# teensy_rfm69cw_nrf_lower.net
KiCad netlist of a schematic drawn in EAGLE
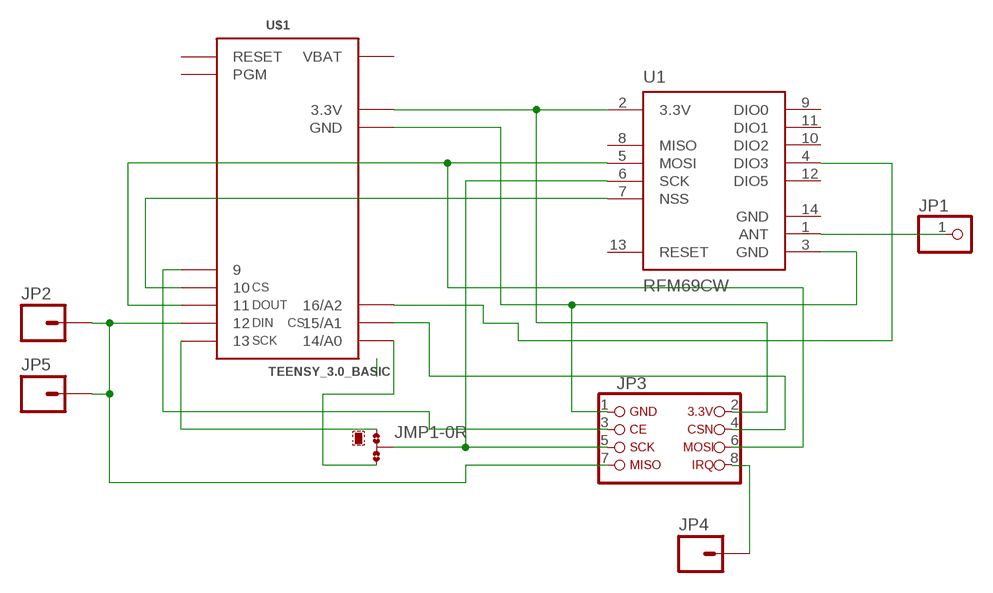
[diagram p0: schematic, sheet 1]

(export (version "E")
  (design (tool "Eeschema 10.0.6"))
  (components
    (comp (ref "JMP1")
      (value "0R-JUMPA")
      (footprint "eagle-import:A0R-JMP")
      (libsource (lib "eagle-import") (part "0R-JUMPA"))
    )
    (comp (ref "JP1")
      (value "PINHD-1X1")
      (footprint "eagle-import:1X01")
      (libsource (lib "eagle-import") (part "PINHD-1X1"))
    )
    (comp (ref "JP2")
      (value "M01SMD-4.5X1.5")
      (footprint "eagle-import:PAD-1.5X4.5")
      (libsource (lib "eagle-import") (part "M01SMD-4.5X1.5"))
    )
    (comp (ref "JP3")
      (value "NRF24")
      (footprint "eagle-import:NRF24")
      (libsource (lib "eagle-import") (part "NRF24"))
    )
    (comp (ref "JP4")
      (value "M01SMD-4.5X1.5")
      (footprint "eagle-import:PAD-1.5X4.5")
      (libsource (lib "eagle-import") (part "M01SMD-4.5X1.5"))
    )
    (comp (ref "JP5")
      (value "M01SMD-4.5X1.5")
      (footprint "eagle-import:PAD-1.5X4.5")
      (libsource (lib "eagle-import") (part "M01SMD-4.5X1.5"))
    )
    (comp (ref "U$1")
      (value "TEENSY_3.0_BASIC")
      (footprint "eagle-import:TEENSY_3.0_BASIC")
      (libsource (lib "eagle-import") (part "TEENSY_3.0_BASIC"))
    )
    (comp (ref "U1")
      (value "RFM69CW")
      (footprint "eagle-import:RFM69CW-XXXS2")
      (libsource (lib "eagle-import") (part "RFM69CW"))
    )
  )
  (nets
    (net (code "1") (name "/GND") (class "Default")
      (node (ref "U1") (pin "14") (pinfunction "GND_14") (pintype "power_in"))
    )
    (net (code "2") (name "/VBAT") (class "Default")
      (node (ref "U$1") (pin "VBAT") (pinfunction "VBAT_VBAT") (pintype "power_in"))
    )
    (net (code "3") (name "Net-(JMP1-Pad1)") (class "Default")
      (node (ref "JMP1") (pin "1") (pinfunction "1_1") (pintype "passive"))
      (node (ref "U$1") (pin "13") (pinfunction "13_13") (pintype "bidirectional"))
    )
    (net (code "4") (name "Net-(JMP1-Pad3)") (class "Default")
      (node (ref "JMP1") (pin "3") (pinfunction "3_3") (pintype "passive"))
      (node (ref "U$1") (pin "14/A0") (pinfunction "14/A0_14/A0") (pintype "bidirectional"))
    )
    (net (code "5") (name "Net-(JP2-1)") (class "Default")
      (node (ref "JP2") (pin "P$1") (pinfunction "1_P$1") (pintype "passive"))
      (node (ref "JP3") (pin "7") (pinfunction "7_7") (pintype "passive"))
      (node (ref "JP5") (pin "P$1") (pinfunction "1_P$1") (pintype "passive"))
      (node (ref "U$1") (pin "12") (pinfunction "12_12") (pintype "bidirectional"))
    )
    (net (code "6") (name "Net-(JP3-Pad3)") (class "Default")
      (node (ref "JP3") (pin "3") (pinfunction "3_3") (pintype "passive"))
      (node (ref "U$1") (pin "9") (pinfunction "9_9") (pintype "bidirectional"))
    )
    (net (code "7") (name "Net-(JP3-Pad4)") (class "Default")
      (node (ref "JP3") (pin "4") (pinfunction "4_4") (pintype "passive"))
      (node (ref "U$1") (pin "15/A1") (pinfunction "15/A1_15/A1") (pintype "bidirectional"))
    )
    (net (code "8") (name "Net-(JP4-1)") (class "Default")
      (node (ref "JP3") (pin "8") (pinfunction "8_8") (pintype "passive"))
      (node (ref "JP4") (pin "P$1") (pinfunction "1_P$1") (pintype "passive"))
    )
    (net (code "9") (name "Net-(U$1-3.3V)") (class "Default")
      (node (ref "JP3") (pin "2") (pinfunction "2_2") (pintype "passive"))
      (node (ref "U$1") (pin "3.3V1") (pinfunction "3.3V_3.3V1") (pintype "power_in"))
      (node (ref "U1") (pin "2") (pinfunction "3.3V_2") (pintype "power_in"))
    )
    (net (code "10") (name "Net-(U$1-GND)") (class "Default")
      (node (ref "JP3") (pin "1") (pinfunction "1_1") (pintype "passive"))
      (node (ref "U$1") (pin "GND1") (pinfunction "GND_GND1") (pintype "power_in"))
      (node (ref "U1") (pin "3") (pinfunction "GND_3") (pintype "power_in"))
    )
    (net (code "11") (name "Net-(U1-ANT)") (class "Default")
      (node (ref "JP1") (pin "1") (pinfunction "1_1") (pintype "passive"))
      (node (ref "U1") (pin "1") (pinfunction "ANT_1") (pintype "passive"))
    )
    (net (code "12") (name "Net-(U1-DIO3)") (class "Default")
      (node (ref "U$1") (pin "16/A2") (pinfunction "16/A2_16/A2") (pintype "bidirectional"))
      (node (ref "U1") (pin "4") (pinfunction "DIO3_4") (pintype "bidirectional"))
    )
    (net (code "13") (name "Net-(U1-MOSI)") (class "Default")
      (node (ref "JP3") (pin "6") (pinfunction "6_6") (pintype "passive"))
      (node (ref "U$1") (pin "11") (pinfunction "11_11") (pintype "bidirectional"))
      (node (ref "U1") (pin "5") (pinfunction "MOSI_5") (pintype "input"))
    )
    (net (code "14") (name "Net-(U1-NSS)") (class "Default")
      (node (ref "U$1") (pin "10") (pinfunction "10_10") (pintype "bidirectional"))
      (node (ref "U1") (pin "7") (pinfunction "NSS_7") (pintype "input"))
    )
    (net (code "15") (name "Net-(U1-SCK)") (class "Default")
      (node (ref "JMP1") (pin "2") (pinfunction "2_2") (pintype "passive"))
      (node (ref "JP3") (pin "5") (pinfunction "5_5") (pintype "passive"))
      (node (ref "U1") (pin "6") (pinfunction "SCK_6") (pintype "input"))
    )
    (net (code "16") (name "unconnected-(U$1-PadPGM)") (class "Default")
      (node (ref "U$1") (pin "PGM") (pinfunction "PGM_PGM") (pintype "bidirectional"))
    )
    (net (code "17") (name "unconnected-(U$1-PadRESET)") (class "Default")
      (node (ref "U$1") (pin "RESET") (pinfunction "RESET_RESET") (pintype "bidirectional"))
    )
    (net (code "18") (name "unconnected-(U1-DIO0-Pad9)") (class "Default")
      (node (ref "U1") (pin "9") (pinfunction "DIO0_9") (pintype "bidirectional"))
    )
    (net (code "19") (name "unconnected-(U1-DIO1-Pad11)") (class "Default")
      (node (ref "U1") (pin "11") (pinfunction "DIO1_11") (pintype "bidirectional"))
    )
    (net (code "20") (name "unconnected-(U1-DIO2-Pad10)") (class "Default")
      (node (ref "U1") (pin "10") (pinfunction "DIO2_10") (pintype "bidirectional"))
    )
    (net (code "21") (name "unconnected-(U1-DIO5-Pad12)") (class "Default")
      (node (ref "U1") (pin "12") (pinfunction "DIO5_12") (pintype "bidirectional"))
    )
    (net (code "22") (name "unconnected-(U1-MISO-Pad8)") (class "Default")
      (node (ref "U1") (pin "8") (pinfunction "MISO_8") (pintype "bidirectional"))
    )
    (net (code "23") (name "unconnected-(U1-RESET-Pad13)") (class "Default")
      (node (ref "U1") (pin "13") (pinfunction "RESET_13") (pintype "input"))
    )
  )
)
